# Schematic.net
KiCad netlist of a schematic drawn in Altium Designer
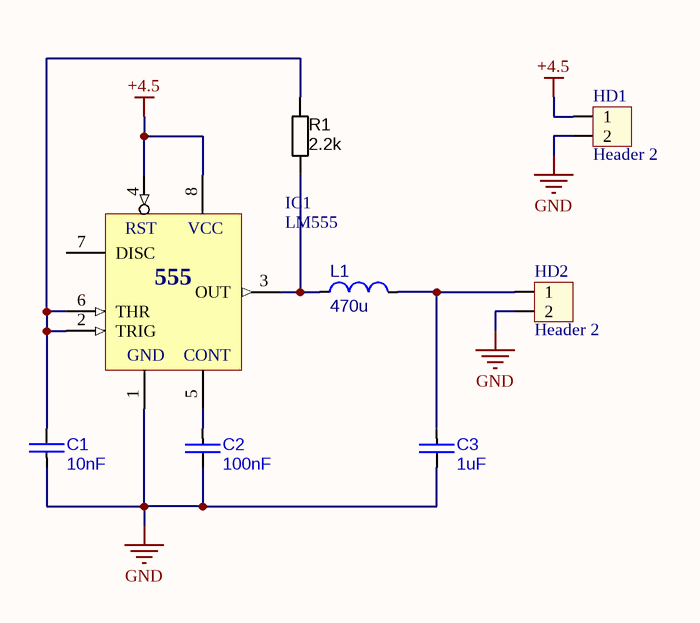
[diagram p0: Schematic.SchDoc]

(export (version "E")
  (design (tool "Eeschema 10.0.6"))
  (components
    (comp (ref "C1")
      (value "10nF")
      (footprint "CAPC2012X135N")
      (description "Capacitor SMD Cer 1.8nF 10% 50V X7R 0805")
      (fields (field (name "TOLERANCE") "±10%") (field (name "Comment") "approved sub OK"))
      (libsource (lib "My library altium") (part "CAP C_0805"))
    )
    (comp (ref "C2")
      (value "100nF")
      (footprint "CAPC2012X135N")
      (description "Capacitor SMD Cer 1.8nF 10% 50V X7R 0805")
      (fields (field (name "TOLERANCE") "±10%") (field (name "Comment") "approved sub OK"))
      (libsource (lib "My library altium") (part "CAP C_0805"))
    )
    (comp (ref "C3")
      (value "1uF")
      (footprint "CAPC2012X135N")
      (description "Capacitor SMD Cer 1.8nF 10% 50V X7R 0805")
      (fields (field (name "TOLERANCE") "±10%") (field (name "Comment") "approved sub OK"))
      (libsource (lib "My library altium") (part "CAP C_0805"))
    )
    (comp (ref "HD1")
      (value "Header 2")
      (footprint "HED2")
      (description "Header 2 (Green)")
      (libsource (lib "My library altium") (part "Header 2"))
    )
    (comp (ref "HD2")
      (value "Header 2")
      (footprint "HED2")
      (description "Header 2 (Green)")
      (libsource (lib "My library altium") (part "Header 2"))
    )
    (comp (ref "IC1")
      (value "LM555")
      (footprint "DIP8/W0.3")
      (description "Timer")
      (libsource (lib "My library altium") (part "LM555"))
    )
    (comp (ref "L1")
      (value "470u")
      (footprint "INDM2520X190N")
      (description "Inductor SMD chip 47nH 1008")
      (fields (field (name "TOLERANCE") "±5%"))
      (libsource (lib "My library altium") (part "Inductor_1008"))
    )
    (comp (ref "R1")
      (value "2.2k")
      (footprint "RESC2012N_ZERO")
      (description "Resistor SMD chip 0.0 Ohm 0.125W 0805")
      (fields (field (name "Comment") "Jumper"))
      (libsource (lib "My library altium") (part "RES_0805"))
    )
  )
  (nets
    (net (code "1") (name "+4.5") (class "Default")
      (node (ref "HD1") (pin "1") (pinfunction "1_1") (pintype "passive"))
      (node (ref "IC1") (pin "4") (pinfunction "RST_4") (pintype "input"))
      (node (ref "IC1") (pin "8") (pinfunction "VCC_8") (pintype "power_in"))
    )
    (net (code "2") (name "GND") (class "Default")
      (node (ref "C1") (pin "1") (pintype "passive"))
      (node (ref "C2") (pin "2") (pintype "passive"))
      (node (ref "C3") (pin "2") (pintype "passive"))
      (node (ref "HD1") (pin "2") (pinfunction "2_2") (pintype "passive"))
      (node (ref "HD2") (pin "2") (pinfunction "2_2") (pintype "passive"))
      (node (ref "IC1") (pin "1") (pinfunction "GND_1") (pintype "power_in"))
    )
    (net (code "3") (name "Net-(C3-Pad1)") (class "Default")
      (node (ref "C3") (pin "1") (pintype "passive"))
      (node (ref "HD2") (pin "1") (pinfunction "1_1") (pintype "passive"))
      (node (ref "L1") (pin "2") (pinfunction "2_2") (pintype "passive"))
    )
    (net (code "4") (name "Net-(IC1-CONT)") (class "Default")
      (node (ref "C2") (pin "1") (pintype "passive"))
      (node (ref "IC1") (pin "5") (pinfunction "CONT_5") (pintype "passive"))
    )
    (net (code "5") (name "Net-(IC1-OUT)") (class "Default")
      (node (ref "IC1") (pin "3") (pinfunction "OUT_3") (pintype "output"))
      (node (ref "L1") (pin "1") (pinfunction "1_1") (pintype "passive"))
      (node (ref "R1") (pin "2") (pinfunction "2_2") (pintype "passive"))
    )
    (net (code "6") (name "Net-(IC1-THR)") (class "Default")
      (node (ref "C1") (pin "2") (pintype "passive"))
      (node (ref "IC1") (pin "2") (pinfunction "TRIG_2") (pintype "input"))
      (node (ref "IC1") (pin "6") (pinfunction "THR_6") (pintype "input"))
      (node (ref "R1") (pin "1") (pinfunction "1_1") (pintype "passive"))
    )
    (net (code "7") (name "unconnected-(IC1-DISC-Pad7)") (class "Default")
      (node (ref "IC1") (pin "7") (pinfunction "DISC_7") (pintype "open_collector"))
    )
  )
)
